# ccnor_stm32_v25-sync-unified-mini.net
KiCad netlist of a schematic drawn in EAGLE
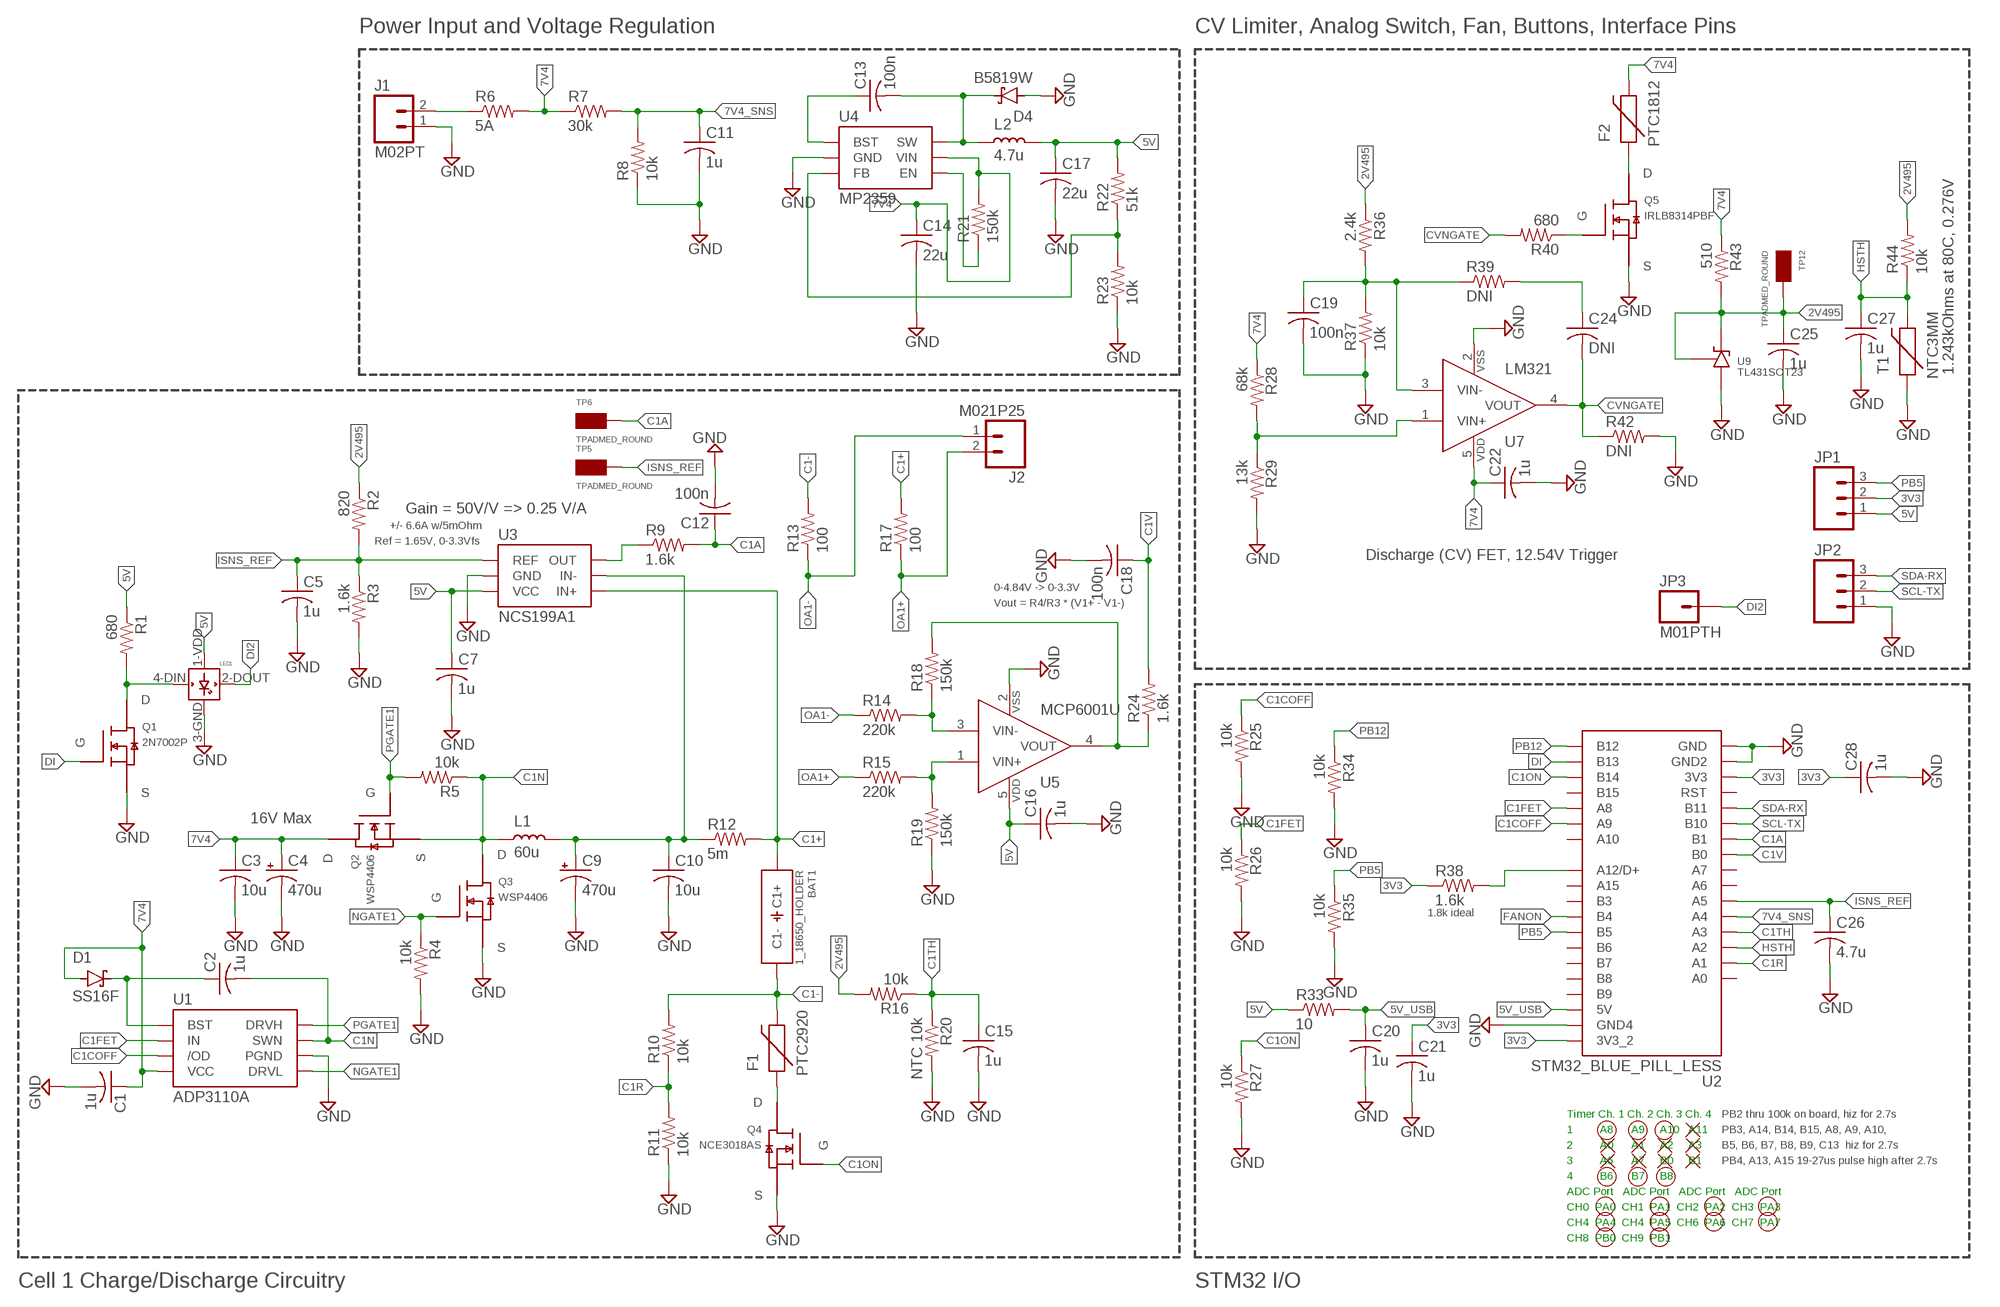
[diagram p0: schematic, sheet 1]

(export (version "E")
  (design (tool "Eeschema 10.0.6"))
  (components
    (comp (ref "BAT1")
      (value "1_18650_HOLDER")
      (footprint "eagle-import:1S_18650_SMD_NH")
      (libsource (lib "eagle-import") (part "1_18650_HOLDER"))
    )
    (comp (ref "C1")
      (value "1u")
      (footprint "eagle-import:C0402")
      (libsource (lib "eagle-import") (part "C-USC0402"))
    )
    (comp (ref "C2")
      (value "1u")
      (footprint "eagle-import:C0603")
      (libsource (lib "eagle-import") (part "C-USC0603"))
    )
    (comp (ref "C3")
      (value "10u")
      (footprint "eagle-import:C1206")
      (libsource (lib "eagle-import") (part "C-USC1206"))
    )
    (comp (ref "C4")
      (value "470u")
      (footprint "eagle-import:E2,5-7")
      (libsource (lib "eagle-import") (part "CPOL-USE2.5-7"))
    )
    (comp (ref "C5")
      (value "1u")
      (footprint "eagle-import:C0402")
      (libsource (lib "eagle-import") (part "C-USC0402"))
    )
    (comp (ref "C7")
      (value "1u")
      (footprint "eagle-import:C0402")
      (libsource (lib "eagle-import") (part "C-USC0402"))
    )
    (comp (ref "C9")
      (value "470u")
      (footprint "eagle-import:E2,5-7")
      (libsource (lib "eagle-import") (part "CPOL-USE2.5-7"))
    )
    (comp (ref "C10")
      (value "10u")
      (footprint "eagle-import:C1206")
      (libsource (lib "eagle-import") (part "C-USC1206"))
    )
    (comp (ref "C11")
      (value "1u")
      (footprint "eagle-import:C0402")
      (libsource (lib "eagle-import") (part "C-USC0402"))
    )
    (comp (ref "C12")
      (value "100n")
      (footprint "eagle-import:C0402")
      (libsource (lib "eagle-import") (part "C-USC0402"))
    )
    (comp (ref "C13")
      (value "100n")
      (footprint "eagle-import:C0402")
      (libsource (lib "eagle-import") (part "C-USC0402"))
    )
    (comp (ref "C14")
      (value "22u")
      (footprint "eagle-import:C0805")
      (libsource (lib "eagle-import") (part "C-USC0805"))
    )
    (comp (ref "C15")
      (value "1u")
      (footprint "eagle-import:C0402")
      (libsource (lib "eagle-import") (part "C-USC0402"))
    )
    (comp (ref "C16")
      (value "1u")
      (footprint "eagle-import:C0402")
      (libsource (lib "eagle-import") (part "C-USC0402"))
    )
    (comp (ref "C17")
      (value "22u")
      (footprint "eagle-import:C0603")
      (libsource (lib "eagle-import") (part "C-USC0603"))
    )
    (comp (ref "C18")
      (value "100n")
      (footprint "eagle-import:C0402")
      (libsource (lib "eagle-import") (part "C-USC0402"))
    )
    (comp (ref "C19")
      (value "100n")
      (footprint "eagle-import:C0402")
      (libsource (lib "eagle-import") (part "C-USC0402"))
    )
    (comp (ref "C20")
      (value "1u")
      (footprint "eagle-import:C0402")
      (libsource (lib "eagle-import") (part "C-USC0402"))
    )
    (comp (ref "C21")
      (value "1u")
      (footprint "eagle-import:C0402")
      (libsource (lib "eagle-import") (part "C-USC0402"))
    )
    (comp (ref "C22")
      (value "1u")
      (footprint "eagle-import:C0402")
      (libsource (lib "eagle-import") (part "C-USC0402"))
    )
    (comp (ref "C24")
      (value "DNI")
      (footprint "eagle-import:C0402")
      (libsource (lib "eagle-import") (part "C-USC0402"))
    )
    (comp (ref "C25")
      (value "1u")
      (footprint "eagle-import:C0402")
      (libsource (lib "eagle-import") (part "C-USC0402"))
    )
    (comp (ref "C26")
      (value "4.7u")
      (footprint "eagle-import:C0402")
      (libsource (lib "eagle-import") (part "C-USC0402"))
    )
    (comp (ref "C27")
      (value "1u")
      (footprint "eagle-import:C0402")
      (libsource (lib "eagle-import") (part "C-USC0402"))
    )
    (comp (ref "C28")
      (value "1u")
      (footprint "eagle-import:C0402")
      (libsource (lib "eagle-import") (part "C-USC0402"))
    )
    (comp (ref "D1")
      (value "SS16F")
      (footprint "eagle-import:SOD123")
      (libsource (lib "eagle-import") (part "DIODE_SCHOTTKYCDBM140-G"))
    )
    (comp (ref "D4")
      (value "B5819W")
      (footprint "eagle-import:SOD123W")
      (libsource (lib "eagle-import") (part "PMEG3020ER"))
    )
    (comp (ref "F1")
      (value "PTC2920")
      (footprint "eagle-import:2920")
      (libsource (lib "eagle-import") (part "PTC2920"))
    )
    (comp (ref "F2")
      (value "PTC1812")
      (footprint "eagle-import:1812")
      (libsource (lib "eagle-import") (part "PTC1812"))
    )
    (comp (ref "J1")
      (value "M02PT")
      (footprint "eagle-import:PHOENIXCONTACT1935161")
      (libsource (lib "eagle-import") (part "M02PT"))
    )
    (comp (ref "J2")
      (value "M021P25")
      (footprint "eagle-import:M02_1P25MM")
      (libsource (lib "eagle-import") (part "M021P25"))
    )
    (comp (ref "JP1")
      (value "M03PTH")
      (footprint "eagle-import:1X03")
      (libsource (lib "eagle-import") (part "M03PTH"))
    )
    (comp (ref "JP2")
      (value "M03PTH")
      (footprint "eagle-import:1X03")
      (libsource (lib "eagle-import") (part "M03PTH"))
    )
    (comp (ref "JP3")
      (value "M01PTH")
      (footprint "eagle-import:1X01")
      (libsource (lib "eagle-import") (part "M01PTH"))
    )
    (comp (ref "L1")
      (value "60u")
      (footprint "eagle-import:INDUCTOR_10A_8.2MMX21MM")
      (libsource (lib "eagle-import") (part "INDUCTOR10A"))
    )
    (comp (ref "L2")
      (value "4.7u")
      (footprint "eagle-import:0805")
      (libsource (lib "eagle-import") (part "INDUCTOR0805"))
    )
    (comp (ref "LED1")
      (value "WS2812B")
      (footprint "eagle-import:WS2812B")
      (libsource (lib "eagle-import") (part "WS2812B"))
    )
    (comp (ref "Q1")
      (value "2N7002P")
      (footprint "eagle-import:SOT23")
      (libsource (lib "eagle-import") (part "2N7002P"))
    )
    (comp (ref "Q2")
      (value "WSP4406")
      (footprint "eagle-import:8-SOIC")
      (libsource (lib "eagle-import") (part "N-MOSFET-SOIC8"))
    )
    (comp (ref "Q3")
      (value "WSP4406")
      (footprint "eagle-import:8-SOIC")
      (libsource (lib "eagle-import") (part "N-MOSFET-SOIC8"))
    )
    (comp (ref "Q4")
      (value "NCE3018AS")
      (footprint "eagle-import:8-SOIC")
      (libsource (lib "eagle-import") (part "N-MOSFET-SOIC8"))
    )
    (comp (ref "Q5")
      (value "IRLB8314PBF")
      (footprint "eagle-import:TO-220")
      (libsource (lib "eagle-import") (part "IRLB8314PBF"))
    )
    (comp (ref "R1")
      (value "680")
      (footprint "eagle-import:R0402")
      (libsource (lib "eagle-import") (part "R-US_R0402"))
    )
    (comp (ref "R2")
      (value "820")
      (footprint "eagle-import:R0402")
      (libsource (lib "eagle-import") (part "R-US_R0402"))
    )
    (comp (ref "R3")
      (value "1.6k")
      (footprint "eagle-import:R0402")
      (libsource (lib "eagle-import") (part "R-US_R0402"))
    )
    (comp (ref "R4")
      (value "10k")
      (footprint "eagle-import:R0402")
      (libsource (lib "eagle-import") (part "R-US_R0402"))
    )
    (comp (ref "R5")
      (value "10k")
      (footprint "eagle-import:R0402")
      (libsource (lib "eagle-import") (part "R-US_R0402"))
    )
    (comp (ref "R6")
      (value "5A")
      (footprint "eagle-import:R1206")
      (libsource (lib "eagle-import") (part "R-US_R1206"))
    )
    (comp (ref "R7")
      (value "30k")
      (footprint "eagle-import:R0402")
      (libsource (lib "eagle-import") (part "R-US_R0402"))
    )
    (comp (ref "R8")
      (value "10k")
      (footprint "eagle-import:R0402")
      (libsource (lib "eagle-import") (part "R-US_R0402"))
    )
    (comp (ref "R9")
      (value "1.6k")
      (footprint "eagle-import:R0402")
      (libsource (lib "eagle-import") (part "R-US_R0402"))
    )
    (comp (ref "R10")
      (value "10k")
      (footprint "eagle-import:R0402")
      (libsource (lib "eagle-import") (part "R-US_R0402"))
    )
    (comp (ref "R11")
      (value "10k")
      (footprint "eagle-import:R0402")
      (libsource (lib "eagle-import") (part "R-US_R0402"))
    )
    (comp (ref "R12")
      (value "5m")
      (footprint "eagle-import:R1206")
      (libsource (lib "eagle-import") (part "R-US_R1206"))
    )
    (comp (ref "R13")
      (value "100")
      (footprint "eagle-import:R0402")
      (libsource (lib "eagle-import") (part "R-US_R0402"))
    )
    (comp (ref "R14")
      (value "220k")
      (footprint "eagle-import:R0402")
      (libsource (lib "eagle-import") (part "R-US_R0402"))
    )
    (comp (ref "R15")
      (value "220k")
      (footprint "eagle-import:R0402")
      (libsource (lib "eagle-import") (part "R-US_R0402"))
    )
    (comp (ref "R16")
      (value "10k")
      (footprint "eagle-import:R0402")
      (libsource (lib "eagle-import") (part "R-US_R0402"))
    )
    (comp (ref "R17")
      (value "100")
      (footprint "eagle-import:R0402")
      (libsource (lib "eagle-import") (part "R-US_R0402"))
    )
    (comp (ref "R18")
      (value "150k")
      (footprint "eagle-import:R0402")
      (libsource (lib "eagle-import") (part "R-US_R0402"))
    )
    (comp (ref "R19")
      (value "150k")
      (footprint "eagle-import:R0402")
      (libsource (lib "eagle-import") (part "R-US_R0402"))
    )
    (comp (ref "R20")
      (value "NTC 10k")
      (footprint "eagle-import:R0402")
      (libsource (lib "eagle-import") (part "R-US_R0402"))
    )
    (comp (ref "R21")
      (value "150k")
      (footprint "eagle-import:R0402")
      (libsource (lib "eagle-import") (part "R-US_R0402"))
    )
    (comp (ref "R22")
      (value "51k")
      (footprint "eagle-import:R0402")
      (libsource (lib "eagle-import") (part "R-US_R0402"))
    )
    (comp (ref "R23")
      (value "10k")
      (footprint "eagle-import:R0402")
      (libsource (lib "eagle-import") (part "R-US_R0402"))
    )
    (comp (ref "R24")
      (value "1.6k")
      (footprint "eagle-import:R0402")
      (libsource (lib "eagle-import") (part "R-US_R0402"))
    )
    (comp (ref "R25")
      (value "10k")
      (footprint "eagle-import:R0402")
      (libsource (lib "eagle-import") (part "R-US_R0402"))
    )
    (comp (ref "R26")
      (value "10k")
      (footprint "eagle-import:R0402")
      (libsource (lib "eagle-import") (part "R-US_R0402"))
    )
    (comp (ref "R27")
      (value "10k")
      (footprint "eagle-import:R0402")
      (libsource (lib "eagle-import") (part "R-US_R0402"))
    )
    (comp (ref "R28")
      (value "68k")
      (footprint "eagle-import:R0402")
      (libsource (lib "eagle-import") (part "R-US_R0402"))
    )
    (comp (ref "R29")
      (value "13k")
      (footprint "eagle-import:R0402")
      (libsource (lib "eagle-import") (part "R-US_R0402"))
    )
    (comp (ref "R33")
      (value "10")
      (footprint "eagle-import:R0402")
      (libsource (lib "eagle-import") (part "R-US_R0402"))
    )
    (comp (ref "R34")
      (value "10k")
      (footprint "eagle-import:R0402")
      (libsource (lib "eagle-import") (part "R-US_R0402"))
    )
    (comp (ref "R35")
      (value "10k")
      (footprint "eagle-import:R0402")
      (libsource (lib "eagle-import") (part "R-US_R0402"))
    )
    (comp (ref "R36")
      (value "2.4k")
      (footprint "eagle-import:R0402")
      (libsource (lib "eagle-import") (part "R-US_R0402"))
    )
    (comp (ref "R37")
      (value "10k")
      (footprint "eagle-import:R0402")
      (libsource (lib "eagle-import") (part "R-US_R0402"))
    )
    (comp (ref "R38")
      (value "1.6k")
      (footprint "eagle-import:R0402")
      (libsource (lib "eagle-import") (part "R-US_R0402"))
    )
    (comp (ref "R39")
      (value "DNI")
      (footprint "eagle-import:R0402")
      (libsource (lib "eagle-import") (part "R-US_R0402"))
    )
    (comp (ref "R40")
      (value "680")
      (footprint "eagle-import:R0402")
      (libsource (lib "eagle-import") (part "R-US_R0402"))
    )
    (comp (ref "R42")
      (value "DNI")
      (footprint "eagle-import:R0402")
      (libsource (lib "eagle-import") (part "R-US_R0402"))
    )
    (comp (ref "R43")
      (value "510")
      (footprint "eagle-import:R0402")
      (libsource (lib "eagle-import") (part "R-US_R0402"))
    )
    (comp (ref "R44")
      (value "10k")
      (footprint "eagle-import:R0402")
      (libsource (lib "eagle-import") (part "R-US_R0402"))
    )
    (comp (ref "T1")
      (value "NTC3MM")
      (footprint "eagle-import:THERMISTOR_3MMX3MM")
      (libsource (lib "eagle-import") (part "PTCNTC3MM"))
    )
    (comp (ref "TP5")
      (value "TPADMED_ROUND")
      (footprint "eagle-import:TPAD_MED_ROUND")
      (libsource (lib "eagle-import") (part "TPADMED_ROUND"))
    )
    (comp (ref "TP6")
      (value "TPADMED_ROUND")
      (footprint "eagle-import:TPAD_MED_ROUND")
      (libsource (lib "eagle-import") (part "TPADMED_ROUND"))
    )
    (comp (ref "TP12")
      (value "TPADMED_ROUND")
      (footprint "eagle-import:TPAD_MED_ROUND")
      (libsource (lib "eagle-import") (part "TPADMED_ROUND"))
    )
    (comp (ref "U1")
      (value "ADP3110A")
      (footprint "eagle-import:8-SOIC")
      (libsource (lib "eagle-import") (part "ADP3110A"))
    )
    (comp (ref "U2")
      (value "STM32_BLUE_PILL_LESS")
      (footprint "eagle-import:STM32_BLUE_PILL_SMD")
      (libsource (lib "eagle-import") (part "STM32_BLUE_PILL_LESS"))
    )
    (comp (ref "U3")
      (value "NCS199A1")
      (footprint "eagle-import:SOT-363")
      (libsource (lib "eagle-import") (part "INA214"))
    )
    (comp (ref "U4")
      (value "MP2359")
      (footprint "eagle-import:SOT23-6")
      (libsource (lib "eagle-import") (part "JW5052C"))
    )
    (comp (ref "U5")
      (value "MCP6001U")
      (footprint "eagle-import:SOT23-5")
      (libsource (lib "eagle-import") (part "MCP6001U"))
    )
    (comp (ref "U7")
      (value "LM321")
      (footprint "eagle-import:SOT23-5")
      (libsource (lib "eagle-import") (part "LM321"))
    )
    (comp (ref "U9")
      (value "TL431SOT23")
      (footprint "eagle-import:SOT23")
      (libsource (lib "eagle-import") (part "TL431SOT23"))
    )
  )
  (nets
    (net (code "1") (name "2V495") (class "Default")
      (node (ref "C25") (pin "1") (pinfunction "1_1") (pintype "passive"))
      (node (ref "R16") (pin "2") (pinfunction "2_2") (pintype "passive"))
      (node (ref "R2") (pin "1") (pinfunction "1_1") (pintype "passive"))
      (node (ref "R36") (pin "1") (pinfunction "1_1") (pintype "passive"))
      (node (ref "R43") (pin "2") (pinfunction "2_2") (pintype "passive"))
      (node (ref "R44") (pin "2") (pinfunction "2_2") (pintype "passive"))
      (node (ref "TP12") (pin "1") (pinfunction "1_1") (pintype "bidirectional"))
      (node (ref "U9") (pin "1") (pinfunction "K_1") (pintype "passive"))
      (node (ref "U9") (pin "2") (pinfunction "REF_2") (pintype "passive"))
    )
    (net (code "2") (name "3V3") (class "Default")
      (node (ref "C21") (pin "1") (pinfunction "1_1") (pintype "passive"))
      (node (ref "C28") (pin "1") (pinfunction "1_1") (pintype "passive"))
      (node (ref "JP1") (pin "2") (pinfunction "2_2") (pintype "passive"))
      (node (ref "R38") (pin "1") (pinfunction "1_1") (pintype "passive"))
      (node (ref "U2") (pin "3V3") (pinfunction "3V3_3V3") (pintype "bidirectional"))
      (node (ref "U2") (pin "3V3_2") (pinfunction "3V3_2_3V3_2") (pintype "bidirectional"))
    )
    (net (code "3") (name "5V") (class "Default")
      (node (ref "C16") (pin "1") (pinfunction "1_1") (pintype "passive"))
      (node (ref "C17") (pin "1") (pinfunction "1_1") (pintype "passive"))
      (node (ref "C7") (pin "1") (pinfunction "1_1") (pintype "passive"))
      (node (ref "JP1") (pin "1") (pinfunction "1_1") (pintype "passive"))
      (node (ref "L2") (pin "2") (pinfunction "P$2_2") (pintype "passive"))
      (node (ref "LED1") (pin "1-VDD") (pinfunction "VDD_1-VDD") (pintype "bidirectional"))
      (node (ref "R1") (pin "1") (pinfunction "1_1") (pintype "passive"))
      (node (ref "R22") (pin "2") (pinfunction "2_2") (pintype "passive"))
      (node (ref "R33") (pin "1") (pinfunction "1_1") (pintype "passive"))
      (node (ref "U3") (pin "3") (pinfunction "VCC_3") (pintype "bidirectional"))
      (node (ref "U5") (pin "5") (pinfunction "VDD_5") (pintype "bidirectional"))
    )
    (net (code "4") (name "5V_USB") (class "Default")
      (node (ref "C20") (pin "1") (pinfunction "1_1") (pintype "passive"))
      (node (ref "R33") (pin "2") (pinfunction "2_2") (pintype "passive"))
      (node (ref "U2") (pin "5V") (pinfunction "5V_5V") (pintype "bidirectional"))
    )
    (net (code "5") (name "7V4") (class "Default")
      (node (ref "C1") (pin "1") (pinfunction "1_1") (pintype "passive"))
      (node (ref "C14") (pin "1") (pinfunction "1_1") (pintype "passive"))
      (node (ref "C22") (pin "1") (pinfunction "1_1") (pintype "passive"))
      (node (ref "C3") (pin "1") (pinfunction "1_1") (pintype "passive"))
      (node (ref "C4") (pin "+") (pinfunction "+_+") (pintype "passive"))
      (node (ref "D1") (pin "A") (pinfunction "ANODE_A") (pintype "passive"))
      (node (ref "F2") (pin "2") (pinfunction "2_2") (pintype "bidirectional"))
      (node (ref "Q2") (pin "5") (pinfunction "D_5") (pintype "bidirectional"))
      (node (ref "Q2") (pin "6") (pinfunction "D_6") (pintype "bidirectional"))
      (node (ref "Q2") (pin "7") (pinfunction "D_7") (pintype "bidirectional"))
      (node (ref "Q2") (pin "8") (pinfunction "D_8") (pintype "bidirectional"))
      (node (ref "R21") (pin "2") (pinfunction "2_2") (pintype "passive"))
      (node (ref "R28") (pin "1") (pinfunction "1_1") (pintype "passive"))
      (node (ref "R43") (pin "1") (pinfunction "1_1") (pintype "passive"))
      (node (ref "R6") (pin "2") (pinfunction "2_2") (pintype "passive"))
      (node (ref "R7") (pin "1") (pinfunction "1_1") (pintype "passive"))
      (node (ref "U1") (pin "4") (pinfunction "VCC_4") (pintype "bidirectional"))
      (node (ref "U4") (pin "5") (pinfunction "VIN_5") (pintype "bidirectional"))
      (node (ref "U7") (pin "5") (pinfunction "VDD_5") (pintype "bidirectional"))
    )
    (net (code "6") (name "7V4_SNS") (class "Default")
      (node (ref "C11") (pin "1") (pinfunction "1_1") (pintype "passive"))
      (node (ref "R7") (pin "2") (pinfunction "2_2") (pintype "passive"))
      (node (ref "R8") (pin "2") (pinfunction "2_2") (pintype "passive"))
      (node (ref "U2") (pin "A4") (pinfunction "A4_A4") (pintype "bidirectional"))
    )
    (net (code "7") (name "C1+") (class "Default")
      (node (ref "BAT1") (pin "1+") (pinfunction "C1+_1+") (pintype "bidirectional"))
      (node (ref "R12") (pin "2") (pinfunction "2_2") (pintype "passive"))
      (node (ref "R17") (pin "2") (pinfunction "2_2") (pintype "passive"))
      (node (ref "U3") (pin "4") (pinfunction "IN+_4") (pintype "bidirectional"))
    )
    (net (code "8") (name "C1-") (class "Default")
      (node (ref "BAT1") (pin "1-") (pinfunction "C1-_1-") (pintype "bidirectional"))
      (node (ref "F1") (pin "K") (pinfunction "2_K") (pintype "bidirectional"))
      (node (ref "R10") (pin "2") (pinfunction "2_2") (pintype "passive"))
      (node (ref "R13") (pin "2") (pinfunction "2_2") (pintype "passive"))
    )
    (net (code "9") (name "C1A") (class "Default")
      (node (ref "C12") (pin "1") (pinfunction "1_1") (pintype "passive"))
      (node (ref "R9") (pin "2") (pinfunction "2_2") (pintype "passive"))
      (node (ref "TP6") (pin "1") (pinfunction "1_1") (pintype "bidirectional"))
      (node (ref "U2") (pin "B1") (pinfunction "B1_B1") (pintype "bidirectional"))
    )
    (net (code "10") (name "C1COFF") (class "Default")
      (node (ref "R25") (pin "1") (pinfunction "1_1") (pintype "passive"))
      (node (ref "U1") (pin "3") (pinfunction "/OD_3") (pintype "bidirectional"))
      (node (ref "U2") (pin "A9") (pinfunction "A9_A9") (pintype "bidirectional"))
    )
    (net (code "11") (name "C1FET") (class "Default")
      (node (ref "R26") (pin "1") (pinfunction "1_1") (pintype "passive"))
      (node (ref "U1") (pin "2") (pinfunction "IN_2") (pintype "bidirectional"))
      (node (ref "U2") (pin "A8") (pinfunction "A8_A8") (pintype "bidirectional"))
    )
    (net (code "12") (name "C1N") (class "Default")
      (node (ref "C2") (pin "2") (pinfunction "2_2") (pintype "passive"))
      (node (ref "L1") (pin "P$1") (pinfunction "P$1_P$1") (pintype "passive"))
      (node (ref "Q2") (pin "1") (pinfunction "S_1") (pintype "bidirectional"))
      (node (ref "Q2") (pin "2") (pinfunction "S_2") (pintype "bidirectional"))
      (node (ref "Q2") (pin "3") (pinfunction "S_3") (pintype "bidirectional"))
      (node (ref "Q3") (pin "5") (pinfunction "D_5") (pintype "bidirectional"))
      (node (ref "Q3") (pin "6") (pinfunction "D_6") (pintype "bidirectional"))
      (node (ref "Q3") (pin "7") (pinfunction "D_7") (pintype "bidirectional"))
      (node (ref "Q3") (pin "8") (pinfunction "D_8") (pintype "bidirectional"))
      (node (ref "R5") (pin "1") (pinfunction "1_1") (pintype "passive"))
      (node (ref "U1") (pin "7") (pinfunction "SWN_7") (pintype "bidirectional"))
    )
    (net (code "13") (name "C1ON") (class "Default")
      (node (ref "Q4") (pin "4") (pinfunction "G_4") (pintype "bidirectional"))
      (node (ref "R27") (pin "1") (pinfunction "1_1") (pintype "passive"))
      (node (ref "U2") (pin "B14") (pinfunction "B14_B14") (pintype "bidirectional"))
    )
    (net (code "14") (name "C1R") (class "Default")
      (node (ref "R10") (pin "1") (pinfunction "1_1") (pintype "passive"))
      (node (ref "R11") (pin "2") (pinfunction "2_2") (pintype "passive"))
      (node (ref "U2") (pin "A1") (pinfunction "A1_A1") (pintype "bidirectional"))
    )
    (net (code "15") (name "C1TH") (class "Default")
      (node (ref "C15") (pin "1") (pinfunction "1_1") (pintype "passive"))
      (node (ref "R16") (pin "1") (pinfunction "1_1") (pintype "passive"))
      (node (ref "R20") (pin "1") (pinfunction "1_1") (pintype "passive"))
      (node (ref "U2") (pin "A3") (pinfunction "A3_A3") (pintype "bidirectional"))
    )
    (net (code "16") (name "C1V") (class "Default")
      (node (ref "C18") (pin "1") (pinfunction "1_1") (pintype "passive"))
      (node (ref "R24") (pin "2") (pinfunction "2_2") (pintype "passive"))
      (node (ref "U2") (pin "B0") (pinfunction "B0_B0") (pintype "bidirectional"))
    )
    (net (code "17") (name "CVNGATE") (class "Default")
      (node (ref "C24") (pin "2") (pinfunction "2_2") (pintype "passive"))
      (node (ref "R40") (pin "2") (pinfunction "2_2") (pintype "passive"))
      (node (ref "R42") (pin "1") (pinfunction "1_1") (pintype "passive"))
      (node (ref "U7") (pin "4") (pinfunction "VOUT_4") (pintype "bidirectional"))
    )
    (net (code "18") (name "DI") (class "Default")
      (node (ref "Q1") (pin "1") (pinfunction "G_1") (pintype "bidirectional"))
      (node (ref "U2") (pin "B13") (pinfunction "B13_B13") (pintype "bidirectional"))
    )
    (net (code "19") (name "DI2") (class "Default")
      (node (ref "JP3") (pin "1") (pinfunction "1_1") (pintype "passive"))
      (node (ref "LED1") (pin "2-DOUT") (pinfunction "DOUT_2-DOUT") (pintype "output"))
    )
    (net (code "20") (name "FANON") (class "Default")
      (node (ref "U2") (pin "B4") (pinfunction "B4_B4") (pintype "bidirectional"))
    )
    (net (code "21") (name "GND") (class "Default")
      (node (ref "C1") (pin "2") (pinfunction "2_2") (pintype "passive"))
      (node (ref "C10") (pin "2") (pinfunction "2_2") (pintype "passive"))
      (node (ref "C11") (pin "2") (pinfunction "2_2") (pintype "passive"))
      (node (ref "C12") (pin "2") (pinfunction "2_2") (pintype "passive"))
      (node (ref "C14") (pin "2") (pinfunction "2_2") (pintype "passive"))
      (node (ref "C15") (pin "2") (pinfunction "2_2") (pintype "passive"))
      (node (ref "C16") (pin "2") (pinfunction "2_2") (pintype "passive"))
      (node (ref "C17") (pin "2") (pinfunction "2_2") (pintype "passive"))
      (node (ref "C18") (pin "2") (pinfunction "2_2") (pintype "passive"))
      (node (ref "C19") (pin "2") (pinfunction "2_2") (pintype "passive"))
      (node (ref "C20") (pin "2") (pinfunction "2_2") (pintype "passive"))
      (node (ref "C21") (pin "2") (pinfunction "2_2") (pintype "passive"))
      (node (ref "C22") (pin "2") (pinfunction "2_2") (pintype "passive"))
      (node (ref "C25") (pin "2") (pinfunction "2_2") (pintype "passive"))
      (node (ref "C26") (pin "2") (pinfunction "2_2") (pintype "passive"))
      (node (ref "C27") (pin "2") (pinfunction "2_2") (pintype "passive"))
      (node (ref "C28") (pin "2") (pinfunction "2_2") (pintype "passive"))
      (node (ref "C3") (pin "2") (pinfunction "2_2") (pintype "passive"))
      (node (ref "C4") (pin "-") (pinfunction "-_-") (pintype "passive"))
      (node (ref "C5") (pin "2") (pinfunction "2_2") (pintype "passive"))
      (node (ref "C7") (pin "2") (pinfunction "2_2") (pintype "passive"))
      (node (ref "C9") (pin "-") (pinfunction "-_-") (pintype "passive"))
      (node (ref "D4") (pin "A") (pinfunction "ANODE_A") (pintype "passive"))
      (node (ref "J1") (pin "1") (pinfunction "1_1") (pintype "passive"))
      (node (ref "JP2") (pin "1") (pinfunction "1_1") (pintype "passive"))
      (node (ref "LED1") (pin "3-GND") (pinfunction "GND_3-GND") (pintype "bidirectional"))
      (node (ref "Q1") (pin "2") (pinfunction "S_2") (pintype "bidirectional"))
      (node (ref "Q3") (pin "1") (pinfunction "S_1") (pintype "bidirectional"))
      (node (ref "Q3") (pin "2") (pinfunction "S_2") (pintype "bidirectional"))
      (node (ref "Q3") (pin "3") (pinfunction "S_3") (pintype "bidirectional"))
      (node (ref "Q4") (pin "1") (pinfunction "S_1") (pintype "bidirectional"))
      (node (ref "Q4") (pin "2") (pinfunction "S_2") (pintype "bidirectional"))
      (node (ref "Q4") (pin "3") (pinfunction "S_3") (pintype "bidirectional"))
      (node (ref "Q5") (pin "3") (pinfunction "S_3") (pintype "bidirectional"))
      (node (ref "R11") (pin "1") (pinfunction "1_1") (pintype "passive"))
      (node (ref "R19") (pin "1") (pinfunction "1_1") (pintype "passive"))
      (node (ref "R20") (pin "2") (pinfunction "2_2") (pintype "passive"))
      (node (ref "R23") (pin "1") (pinfunction "1_1") (pintype "passive"))
      (node (ref "R25") (pin "2") (pinfunction "2_2") (pintype "passive"))
      (node (ref "R26") (pin "2") (pinfunction "2_2") (pintype "passive"))
      (node (ref "R27") (pin "2") (pinfunction "2_2") (pintype "passive"))
      (node (ref "R29") (pin "2") (pinfunction "2_2") (pintype "passive"))
      (node (ref "R3") (pin "2") (pinfunction "2_2") (pintype "passive"))
      (node (ref "R34") (pin "2") (pinfunction "2_2") (pintype "passive"))
      (node (ref "R35") (pin "2") (pinfunction "2_2") (pintype "passive"))
      (node (ref "R37") (pin "1") (pinfunction "1_1") (pintype "passive"))
      (node (ref "R4") (pin "2") (pinfunction "2_2") (pintype "passive"))
      (node (ref "R42") (pin "2") (pinfunction "2_2") (pintype "passive"))
      (node (ref "R8") (pin "1") (pinfunction "1_1") (pintype "passive"))
      (node (ref "T1") (pin "1") (pinfunction "1_1") (pintype "bidirectional"))
      (node (ref "U1") (pin "6") (pinfunction "PGND_6") (pintype "bidirectional"))
      (node (ref "U2") (pin "GND") (pinfunction "GND_GND") (pintype "bidirectional"))
      (node (ref "U2") (pin "GND2") (pinfunction "GND2_GND2") (pintype "bidirectional"))
      (node (ref "U2") (pin "GND4") (pinfunction "GND4_GND4") (pintype "bidirectional"))
      (node (ref "U3") (pin "2") (pinfunction "GND_2") (pintype "bidirectional"))
      (node (ref "U4") (pin "2") (pinfunction "GND_2") (pintype "bidirectional"))
      (node (ref "U5") (pin "2") (pinfunction "VSS_2") (pintype "bidirectional"))
      (node (ref "U7") (pin "2") (pinfunction "VSS_2") (pintype "bidirectional"))
      (node (ref "U9") (pin "3") (pinfunction "A_3") (pintype "passive"))
    )
    (net (code "22") (name "HSTH") (class "Default")
      (node (ref "C27") (pin "1") (pinfunction "1_1") (pintype "passive"))
      (node (ref "R44") (pin "1") (pinfunction "1_1") (pintype "passive"))
      (node (ref "T1") (pin "2") (pinfunction "2_2") (pintype "bidirectional"))
      (node (ref "U2") (pin "A2") (pinfunction "A2_A2") (pintype "bidirectional"))
    )
    (net (code "23") (name "ISNS_REF") (class "Default")
      (node (ref "C26") (pin "1") (pinfunction "1_1") (pintype "passive"))
      (node (ref "C5") (pin "1") (pinfunction "1_1") (pintype "passive"))
      (node (ref "R2") (pin "2") (pinfunction "2_2") (pintype "passive"))
      (node (ref "R3") (pin "1") (pinfunction "1_1") (pintype "passive"))
      (node (ref "TP5") (pin "1") (pinfunction "1_1") (pintype "bidirectional"))
      (node (ref "U2") (pin "A5") (pinfunction "A5_A5") (pintype "bidirectional"))
      (node (ref "U3") (pin "1") (pinfunction "REF_1") (pintype "bidirectional"))
    )
    (net (code "24") (name "NGATE1") (class "Default")
      (node (ref "Q3") (pin "4") (pinfunction "G_4") (pintype "bidirectional"))
      (node (ref "R4") (pin "1") (pinfunction "1_1") (pintype "passive"))
      (node (ref "U1") (pin "5") (pinfunction "DRVL_5") (pintype "bidirectional"))
    )
    (net (code "25") (name "Net-(C24-Pad1)") (class "Default")
      (node (ref "C24") (pin "1") (pinfunction "1_1") (pintype "passive"))
      (node (ref "R39") (pin "2") (pinfunction "2_2") (pintype "passive"))
    )
    (net (code "26") (name "Net-(D1-CATHODE)") (class "Default")
      (node (ref "C2") (pin "1") (pinfunction "1_1") (pintype "passive"))
      (node (ref "D1") (pin "K") (pinfunction "CATHODE_K") (pintype "passive"))
      (node (ref "U1") (pin "1") (pinfunction "BST_1") (pintype "bidirectional"))
    )
    (net (code "27") (name "Net-(D4-CATHODE)") (class "Default")
      (node (ref "C13") (pin "2") (pinfunction "2_2") (pintype "passive"))
      (node (ref "D4") (pin "K") (pinfunction "CATHODE_K") (pintype "passive"))
      (node (ref "L2") (pin "1") (pinfunction "P$1_1") (pintype "passive"))
      (node (ref "U4") (pin "6") (pinfunction "SW_6") (pintype "bidirectional"))
    )
    (net (code "28") (name "Net-(F1-1)") (class "Default")
      (node (ref "F1") (pin "A") (pinfunction "1_A") (pintype "bidirectional"))
      (node (ref "Q4") (pin "5") (pinfunction "D_5") (pintype "bidirectional"))
      (node (ref "Q4") (pin "6") (pinfunction "D_6") (pintype "bidirectional"))
      (node (ref "Q4") (pin "7") (pinfunction "D_7") (pintype "bidirectional"))
      (node (ref "Q4") (pin "8") (pinfunction "D_8") (pintype "bidirectional"))
    )
    (net (code "29") (name "Net-(J1-Pad2)") (class "Default")
      (node (ref "J1") (pin "2") (pinfunction "2_2") (pintype "passive"))
      (node (ref "R6") (pin "1") (pinfunction "1_1") (pintype "passive"))
    )
    (net (code "30") (name "Net-(LED1-DIN)") (class "Default")
      (node (ref "LED1") (pin "4-DIN") (pinfunction "DIN_4-DIN") (pintype "input"))
      (node (ref "Q1") (pin "3") (pinfunction "D_3") (pintype "bidirectional"))
      (node (ref "R1") (pin "2") (pinfunction "2_2") (pintype "passive"))
    )
    (net (code "31") (name "Net-(Q5-D)") (class "Default")
      (node (ref "F2") (pin "1") (pinfunction "1_1") (pintype "bidirectional"))
      (node (ref "Q5") (pin "2") (pinfunction "D_2") (pintype "bidirectional"))
    )
    (net (code "32") (name "Net-(Q5-G)") (class "Default")
      (node (ref "Q5") (pin "1") (pinfunction "G_1") (pintype "bidirectional"))
      (node (ref "R40") (pin "1") (pinfunction "1_1") (pintype "passive"))
    )
    (net (code "33") (name "Net-(U2-A12{slash}D+)") (class "Default")
      (node (ref "R38") (pin "2") (pinfunction "2_2") (pintype "passive"))
      (node (ref "U2") (pin "A12") (pinfunction "A12/D+_A12") (pintype "bidirectional"))
    )
    (net (code "34") (name "Net-(U3-IN-)") (class "Default")
      (node (ref "C10") (pin "1") (pinfunction "1_1") (pintype "passive"))
      (node (ref "C9") (pin "+") (pinfunction "+_+") (pintype "passive"))
      (node (ref "L1") (pin "P$2") (pinfunction "P$2_P$2") (pintype "passive"))
      (node (ref "R12") (pin "1") (pinfunction "1_1") (pintype "passive"))
      (node (ref "U3") (pin "5") (pinfunction "IN-_5") (pintype "bidirectional"))
    )
    (net (code "35") (name "Net-(U3-OUT)") (class "Default")
      (node (ref "R9") (pin "1") (pinfunction "1_1") (pintype "passive"))
      (node (ref "U3") (pin "6") (pinfunction "OUT_6") (pintype "bidirectional"))
    )
    (net (code "36") (name "Net-(U4-BST)") (class "Default")
      (node (ref "C13") (pin "1") (pinfunction "1_1") (pintype "passive"))
      (node (ref "U4") (pin "1") (pinfunction "BST_1") (pintype "bidirectional"))
    )
    (net (code "37") (name "Net-(U4-EN)") (class "Default")
      (node (ref "R21") (pin "1") (pinfunction "1_1") (pintype "passive"))
      (node (ref "U4") (pin "4") (pinfunction "EN_4") (pintype "bidirectional"))
    )
    (net (code "38") (name "Net-(U4-FB)") (class "Default")
      (node (ref "R22") (pin "1") (pinfunction "1_1") (pintype "passive"))
      (node (ref "R23") (pin "2") (pinfunction "2_2") (pintype "passive"))
      (node (ref "U4") (pin "3") (pinfunction "FB_3") (pintype "bidirectional"))
    )
    (net (code "39") (name "Net-(U5-VIN+)") (class "Default")
      (node (ref "R15") (pin "2") (pinfunction "2_2") (pintype "passive"))
      (node (ref "R19") (pin "2") (pinfunction "2_2") (pintype "passive"))
      (node (ref "U5") (pin "1") (pinfunction "VIN+_1") (pintype "bidirectional"))
    )
    (net (code "40") (name "Net-(U5-VIN-)") (class "Default")
      (node (ref "R14") (pin "2") (pinfunction "2_2") (pintype "passive"))
      (node (ref "R18") (pin "1") (pinfunction "1_1") (pintype "passive"))
      (node (ref "U5") (pin "3") (pinfunction "VIN-_3") (pintype "bidirectional"))
    )
    (net (code "41") (name "Net-(U5-VOUT)") (class "Default")
      (node (ref "R18") (pin "2") (pinfunction "2_2") (pintype "passive"))
      (node (ref "R24") (pin "1") (pinfunction "1_1") (pintype "passive"))
      (node (ref "U5") (pin "4") (pinfunction "VOUT_4") (pintype "bidirectional"))
    )
    (net (code "42") (name "Net-(U7-VIN+)") (class "Default")
      (node (ref "R28") (pin "2") (pinfunction "2_2") (pintype "passive"))
      (node (ref "R29") (pin "1") (pinfunction "1_1") (pintype "passive"))
      (node (ref "U7") (pin "1") (pinfunction "VIN+_1") (pintype "bidirectional"))
    )
    (net (code "43") (name "Net-(U7-VIN-)") (class "Default")
      (node (ref "C19") (pin "1") (pinfunction "1_1") (pintype "passive"))
      (node (ref "R36") (pin "2") (pinfunction "2_2") (pintype "passive"))
      (node (ref "R37") (pin "2") (pinfunction "2_2") (pintype "passive"))
      (node (ref "R39") (pin "1") (pinfunction "1_1") (pintype "passive"))
      (node (ref "U7") (pin "3") (pinfunction "VIN-_3") (pintype "bidirectional"))
    )
    (net (code "44") (name "OA1+") (class "Default")
      (node (ref "J2") (pin "2") (pinfunction "2_2") (pintype "passive"))
      (node (ref "R15") (pin "1") (pinfunction "1_1") (pintype "passive"))
      (node (ref "R17") (pin "1") (pinfunction "1_1") (pintype "passive"))
    )
    (net (code "45") (name "OA1-") (class "Default")
      (node (ref "J2") (pin "1") (pinfunction "1_1") (pintype "passive"))
      (node (ref "R13") (pin "1") (pinfunction "1_1") (pintype "passive"))
      (node (ref "R14") (pin "1") (pinfunction "1_1") (pintype "passive"))
    )
    (net (code "46") (name "PB5") (class "Default")
      (node (ref "JP1") (pin "3") (pinfunction "3_3") (pintype "passive"))
      (node (ref "R35") (pin "1") (pinfunction "1_1") (pintype "passive"))
      (node (ref "U2") (pin "B5") (pinfunction "B5_B5") (pintype "bidirectional"))
    )
    (net (code "47") (name "PB12") (class "Default")
      (node (ref "R34") (pin "1") (pinfunction "1_1") (pintype "passive"))
      (node (ref "U2") (pin "B12") (pinfunction "B12_B12") (pintype "bidirectional"))
    )
    (net (code "48") (name "PGATE1") (class "Default")
      (node (ref "Q2") (pin "4") (pinfunction "G_4") (pintype "bidirectional"))
      (node (ref "R5") (pin "2") (pinfunction "2_2") (pintype "passive"))
      (node (ref "U1") (pin "8") (pinfunction "DRVH_8") (pintype "bidirectional"))
    )
    (net (code "49") (name "SCL-TX") (class "Default")
      (node (ref "JP2") (pin "2") (pinfunction "2_2") (pintype "passive"))
      (node (ref "U2") (pin "B10") (pinfunction "B10_B10") (pintype "bidirectional"))
    )
    (net (code "50") (name "SDA-RX") (class "Default")
      (node (ref "JP2") (pin "3") (pinfunction "3_3") (pintype "passive"))
      (node (ref "U2") (pin "B11") (pinfunction "B11_B11") (pintype "bidirectional"))
    )
    (net (code "51") (name "unconnected-(U2-PadA0)") (class "Default")
      (node (ref "U2") (pin "A0") (pinfunction "A0_A0") (pintype "bidirectional"))
    )
    (net (code "52") (name "unconnected-(U2-PadA6)") (class "Default")
      (node (ref "U2") (pin "A6") (pinfunction "A6_A6") (pintype "bidirectional"))
    )
    (net (code "53") (name "unconnected-(U2-PadA7)") (class "Default")
      (node (ref "U2") (pin "A7") (pinfunction "A7_A7") (pintype "bidirectional"))
    )
    (net (code "54") (name "unconnected-(U2-PadA10)") (class "Default")
      (node (ref "U2") (pin "A10") (pinfunction "A10_A10") (pintype "bidirectional"))
    )
    (net (code "55") (name "unconnected-(U2-PadA15)") (class "Default")
      (node (ref "U2") (pin "A15") (pinfunction "A15_A15") (pintype "bidirectional"))
    )
    (net (code "56") (name "unconnected-(U2-PadB3)") (class "Default")
      (node (ref "U2") (pin "B3") (pinfunction "B3_B3") (pintype "bidirectional"))
    )
    (net (code "57") (name "unconnected-(U2-PadB6)") (class "Default")
      (node (ref "U2") (pin "B6") (pinfunction "B6_B6") (pintype "bidirectional"))
    )
    (net (code "58") (name "unconnected-(U2-PadB7)") (class "Default")
      (node (ref "U2") (pin "B7") (pinfunction "B7_B7") (pintype "bidirectional"))
    )
    (net (code "59") (name "unconnected-(U2-PadB8)") (class "Default")
      (node (ref "U2") (pin "B8") (pinfunction "B8_B8") (pintype "bidirectional"))
    )
    (net (code "60") (name "unconnected-(U2-PadB9)") (class "Default")
      (node (ref "U2") (pin "B9") (pinfunction "B9_B9") (pintype "bidirectional"))
    )
    (net (code "61") (name "unconnected-(U2-PadB15)") (class "Default")
      (node (ref "U2") (pin "B15") (pinfunction "B15_B15") (pintype "bidirectional"))
    )
    (net (code "62") (name "unconnected-(U2-PadRST)") (class "Default")
      (node (ref "U2") (pin "RST") (pinfunction "RST_RST") (pintype "bidirectional"))
    )
  )
)
